# ORing.net
KiCad netlist of a schematic drawn in Altium Designer
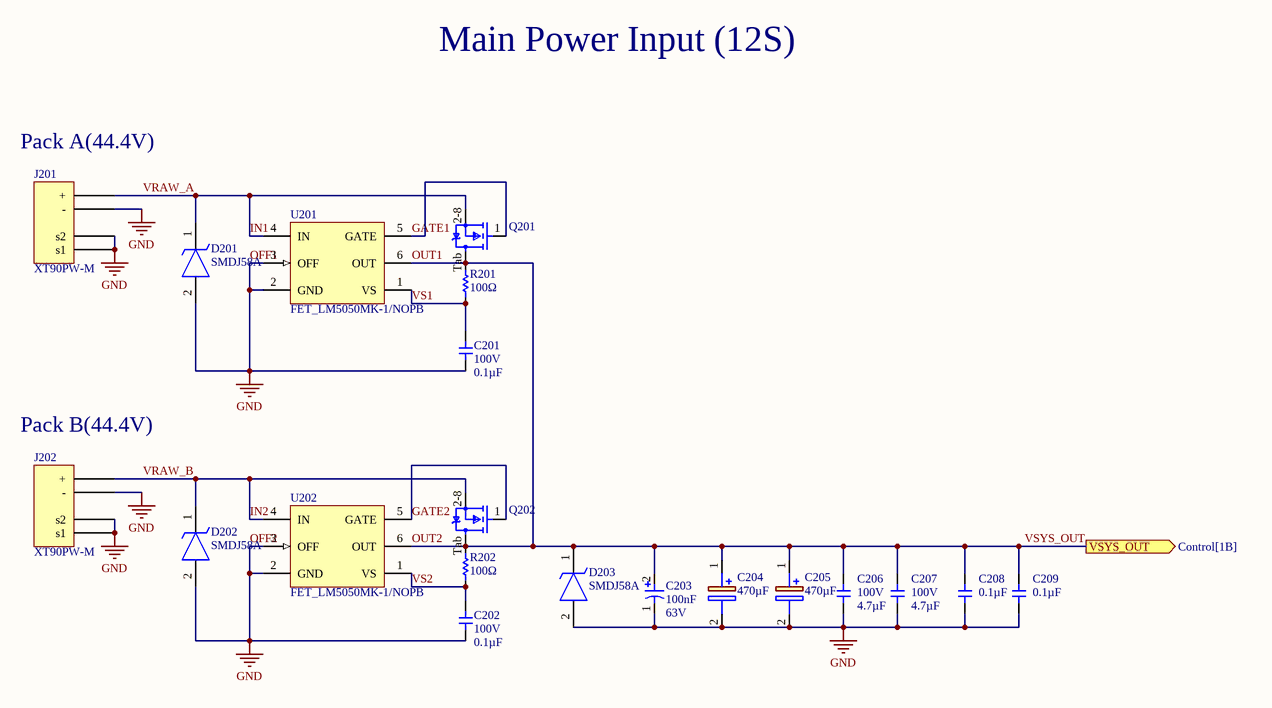
[diagram p0: ORing.SchDoc]

(export (version "E")
  (design (tool "Eeschema 10.0.6"))
  (components
    (comp (ref "C201")
      (value "non-polar_Capacitor")
      (footprint "1206")
      (description "SMD type ceramic capacitor")
      (fields
        (field (name "VOLTAGE") "100V")
        (field (name "CAPACITANCE") "0.1µF")
        (field (name "SOURCE") "robit_passive.SchLib")
      )
      (libsource (lib "robit circuit") (part "Capacitor"))
    )
    (comp (ref "C202")
      (value "non-polar_Capacitor")
      (footprint "1206")
      (description "SMD type ceramic capacitor")
      (fields
        (field (name "VOLTAGE") "100V")
        (field (name "CAPACITANCE") "0.1µF")
        (field (name "SOURCE") "robit_passive.SchLib")
      )
      (libsource (lib "robit circuit") (part "Capacitor"))
    )
    (comp (ref "C203")
      (value "Capacitor_tantal")
      (footprint "SMD_Capacitor_tantal")
      (description "SMD type tantalum capacitor")
      (fields
        (field (name "CAPACITANCE") "100nF")
        (field (name "VOLTAGE") "63V")
        (field (name "SOURCE") "robit_passive.SchLib")
      )
      (libsource (lib "robit circuit") (part "Capacitor_tantal"))
    )
    (comp (ref "C204")
      (value "470µF")
      (footprint "SamacSys:CAPAE1900X2200N")
      (description "Capacitor Polarised")
      (fields
        (field (name "MANUFACTURER_PART_NUMBER") "MAL215099913E3")
        (field (name "MOUSER PART NUMBER") "594-MAL215099913E3")
      )
      (libsource (lib "*") (part "MAL215099913E3"))
    )
    (comp (ref "C205")
      (value "470µF")
      (footprint "SamacSys:CAPAE1900X2200N")
      (description "Capacitor Polarised")
      (fields
        (field (name "MANUFACTURER_PART_NUMBER") "MAL215099913E3")
        (field (name "MOUSER PART NUMBER") "594-MAL215099913E3")
      )
      (libsource (lib "*") (part "MAL215099913E3"))
    )
    (comp (ref "C206")
      (value "non-polar_Capacitor")
      (footprint "1210")
      (description "SMD type ceramic capacitor")
      (fields
        (field (name "VOLTAGE") "100V")
        (field (name "CAPACITANCE") "4.7µF")
        (field (name "SOURCE") "robit_passive.SchLib")
      )
      (libsource (lib "robit circuit") (part "Capacitor"))
    )
    (comp (ref "C207")
      (value "non-polar_Capacitor")
      (footprint "1210")
      (description "SMD type ceramic capacitor")
      (fields
        (field (name "VOLTAGE") "100V")
        (field (name "CAPACITANCE") "4.7µF")
        (field (name "SOURCE") "robit_passive.SchLib")
      )
      (libsource (lib "robit circuit") (part "Capacitor"))
    )
    (comp (ref "C208")
      (value "non-polar_Capacitor")
      (footprint "0603")
      (description "SMD type ceramic capacitor")
      (fields
        (field (name "VOLTAGE") "100V")
        (field (name "CAPACITANCE") "0.1µF")
        (field (name "SOURCE") "robit_passive.SchLib")
      )
      (libsource (lib "robit circuit") (part "Capacitor"))
    )
    (comp (ref "C209")
      (value "non-polar_Capacitor")
      (footprint "0603")
      (description "SMD type ceramic capacitor")
      (fields
        (field (name "VOLTAGE") "100V")
        (field (name "CAPACITANCE") "0.1µF")
        (field (name "SOURCE") "robit_passive.SchLib")
      )
      (libsource (lib "robit circuit") (part "Capacitor"))
    )
    (comp (ref "D201")
      (value "SMDJ58A")
      (footprint "SamacSys:DIONM7959X262N")
      (description "TVS Diode (Uni-directional)")
      (fields (field (name "MOUSER PART NUMBER") "576-SMDJ58A"))
      (libsource (lib "*") (part "SMDJ58A"))
    )
    (comp (ref "D202")
      (value "SMDJ58A")
      (footprint "SamacSys:DIONM7959X262N")
      (description "TVS Diode (Uni-directional)")
      (fields (field (name "MOUSER PART NUMBER") "576-SMDJ58A"))
      (libsource (lib "*") (part "SMDJ58A"))
    )
    (comp (ref "D203")
      (value "SMDJ58A")
      (footprint "SamacSys:DIONM7959X262N")
      (description "TVS Diode (Uni-directional)")
      (fields (field (name "MOUSER PART NUMBER") "576-SMDJ58A"))
      (libsource (lib "*") (part "SMDJ58A"))
    )
    (comp (ref "J201")
      (value "XT90PW-M")
      (footprint "AMASS_XT90PW-M")
      (description "Socket; DC supply; XT90; male; PIN: 2; on PCBs; THT; Colour: yellow")
      (fields (field (name "MF") "AMASS"))
      (libsource (lib "robit circuit") (part "XT90PW-M"))
    )
    (comp (ref "J202")
      (value "XT90PW-M")
      (footprint "AMASS_XT90PW-M")
      (description "Socket; DC supply; XT90; male; PIN: 2; on PCBs; THT; Colour: yellow")
      (fields (field (name "MF") "AMASS"))
      (libsource (lib "robit circuit") (part "XT90PW-M"))
    )
    (comp (ref "Q201")
      (value "Trans_Infineon_IPT015N10N5_eec")
      (footprint "Infineon_IPT015N10N5_0")
      (description "TRANS MOSFET N-CH 100V 300A 8HSOF")
      (fields (field (name "PART NUMBER") "IPT015N10N5") (field (name "MANUFACTURER") "Infineon"))
      (libsource (lib "Trans_Infineon_IPT015N10N5_eec") (part "Trans_Infineon_IPT015N10N5_eec"))
    )
    (comp (ref "Q202")
      (value "Trans_Infineon_IPT015N10N5_eec")
      (footprint "Infineon_IPT015N10N5_0")
      (description "TRANS MOSFET N-CH 100V 300A 8HSOF")
      (fields (field (name "PART NUMBER") "IPT015N10N5") (field (name "MANUFACTURER") "Infineon"))
      (libsource (lib "Trans_Infineon_IPT015N10N5_eec") (part "Trans_Infineon_IPT015N10N5_eec"))
    )
    (comp (ref "R201")
      (value "Resistor")
      (footprint "0603")
      (description "SMD type resistor")
      (fields (field (name "RESISTANCE") "100Ω") (field (name "SOURCE") "robit_passive.SchLib"))
      (libsource (lib "robit circuit") (part "Resistor"))
    )
    (comp (ref "R202")
      (value "Resistor")
      (footprint "0603")
      (description "SMD type resistor")
      (fields (field (name "RESISTANCE") "100Ω") (field (name "SOURCE") "robit_passive.SchLib"))
      (libsource (lib "robit circuit") (part "Resistor"))
    )
    (comp (ref "U201")
      (value "FET_LM5050MK-1/NOPB")
      (footprint "DDC0006A_M")
      (description "5-V to 75-V 400-uA IQ ORing FET controller 6-SOT-23-THIN -40 to 125")
      (libsource (lib "robit circuit") (part "PM-SMPS-LM5050-IL6"))
    )
    (comp (ref "U202")
      (value "FET_LM5050MK-1/NOPB")
      (footprint "DDC0006A_M")
      (description "5-V to 75-V 400-uA IQ ORing FET controller 6-SOT-23-THIN -40 to 125")
      (libsource (lib "robit circuit") (part "PM-SMPS-LM5050-IL6"))
    )
  )
  (nets
    (net (code "1") (name "/GATE1") (class "Default")
      (node (ref "Q201") (pin "1") (pinfunction "Gate_1") (pintype "passive"))
      (node (ref "U201") (pin "5") (pinfunction "GATE_5") (pintype "power_in"))
    )
    (net (code "2") (name "/GATE2") (class "Default")
      (node (ref "Q202") (pin "1") (pinfunction "Gate_1") (pintype "passive"))
      (node (ref "U202") (pin "5") (pinfunction "GATE_5") (pintype "power_in"))
    )
    (net (code "3") (name "/IN1") (class "Default")
      (node (ref "D201") (pin "1") (pinfunction "K_1") (pintype "passive"))
      (node (ref "J201") (pin "P") (pinfunction "+_P") (pintype "power_in"))
      (node (ref "Q201") (pin "2-8") (pinfunction "Source_2-8") (pintype "passive"))
      (node (ref "U201") (pin "4") (pinfunction "IN_4") (pintype "power_in"))
    )
    (net (code "4") (name "/IN2") (class "Default")
      (node (ref "D202") (pin "1") (pinfunction "K_1") (pintype "passive"))
      (node (ref "J202") (pin "P") (pinfunction "+_P") (pintype "power_in"))
      (node (ref "Q202") (pin "2-8") (pinfunction "Source_2-8") (pintype "passive"))
      (node (ref "U202") (pin "4") (pinfunction "IN_4") (pintype "power_in"))
    )
    (net (code "5") (name "/OUT1") (class "Default")
      (node (ref "C203") (pin "2") (pinfunction "1_2") (pintype "passive"))
      (node (ref "C204") (pin "1") (pinfunction "+_1") (pintype "passive"))
      (node (ref "C205") (pin "1") (pinfunction "+_1") (pintype "passive"))
      (node (ref "C206") (pin "1") (pinfunction "1_1") (pintype "passive"))
      (node (ref "C207") (pin "2") (pinfunction "2_2") (pintype "passive"))
      (node (ref "C208") (pin "2") (pinfunction "2_2") (pintype "passive"))
      (node (ref "C209") (pin "2") (pinfunction "2_2") (pintype "passive"))
      (node (ref "D203") (pin "1") (pinfunction "K_1") (pintype "passive"))
      (node (ref "Q201") (pin "Tab") (pinfunction "Drain_Tab") (pintype "passive"))
      (node (ref "Q202") (pin "Tab") (pinfunction "Drain_Tab") (pintype "passive"))
      (node (ref "R201") (pin "2") (pinfunction "2_2") (pintype "passive"))
      (node (ref "R202") (pin "2") (pinfunction "2_2") (pintype "passive"))
      (node (ref "U201") (pin "6") (pinfunction "OUT_6") (pintype "passive"))
      (node (ref "U202") (pin "6") (pinfunction "OUT_6") (pintype "passive"))
    )
    (net (code "6") (name "/VS1") (class "Default")
      (node (ref "C201") (pin "2") (pinfunction "2_2") (pintype "passive"))
      (node (ref "R201") (pin "1") (pinfunction "1_1") (pintype "passive"))
      (node (ref "U201") (pin "1") (pinfunction "VS_1") (pintype "power_in"))
    )
    (net (code "7") (name "/VS2") (class "Default")
      (node (ref "C202") (pin "2") (pinfunction "2_2") (pintype "passive"))
      (node (ref "R202") (pin "1") (pinfunction "1_1") (pintype "passive"))
      (node (ref "U202") (pin "1") (pinfunction "VS_1") (pintype "power_in"))
    )
    (net (code "8") (name "GND") (class "Default")
      (node (ref "C201") (pin "1") (pinfunction "1_1") (pintype "passive"))
      (node (ref "C202") (pin "1") (pinfunction "1_1") (pintype "passive"))
      (node (ref "C203") (pin "1") (pinfunction "0_1") (pintype "passive"))
      (node (ref "C204") (pin "2") (pinfunction "-_2") (pintype "passive"))
      (node (ref "C205") (pin "2") (pinfunction "-_2") (pintype "passive"))
      (node (ref "C206") (pin "2") (pinfunction "2_2") (pintype "passive"))
      (node (ref "C207") (pin "1") (pinfunction "1_1") (pintype "passive"))
      (node (ref "C208") (pin "1") (pinfunction "1_1") (pintype "passive"))
      (node (ref "C209") (pin "1") (pinfunction "1_1") (pintype "passive"))
      (node (ref "D201") (pin "2") (pinfunction "A_2") (pintype "passive"))
      (node (ref "D202") (pin "2") (pinfunction "A_2") (pintype "passive"))
      (node (ref "D203") (pin "2") (pinfunction "A_2") (pintype "passive"))
      (node (ref "J201") (pin "N") (pinfunction "-_N") (pintype "power_in"))
      (node (ref "J201") (pin "S1") (pinfunction "s1_S1") (pintype "power_in"))
      (node (ref "J201") (pin "S2") (pinfunction "s2_S2") (pintype "power_in"))
      (node (ref "J202") (pin "N") (pinfunction "-_N") (pintype "power_in"))
      (node (ref "J202") (pin "S1") (pinfunction "s1_S1") (pintype "power_in"))
      (node (ref "J202") (pin "S2") (pinfunction "s2_S2") (pintype "power_in"))
      (node (ref "U201") (pin "2") (pinfunction "GND_2") (pintype "power_in"))
      (node (ref "U201") (pin "3") (pinfunction "OFF_3") (pintype "input"))
      (node (ref "U202") (pin "2") (pinfunction "GND_2") (pintype "power_in"))
      (node (ref "U202") (pin "3") (pinfunction "OFF_3") (pintype "input"))
    )
  )
)
